# puma_tpc_sipm16.net
KiCad netlist of a schematic drawn in EAGLE
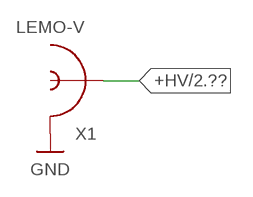
[diagram p0: schematic, sheet 1]
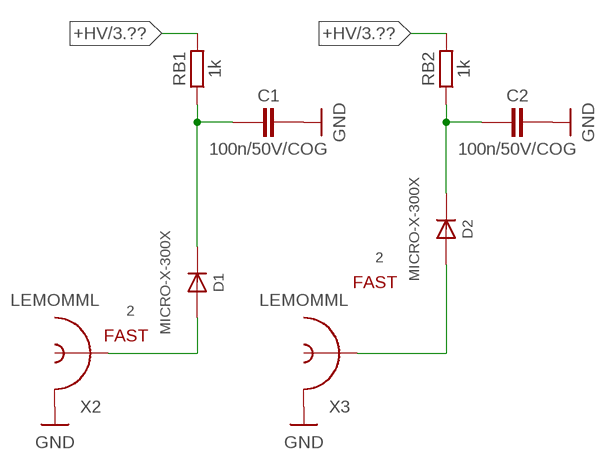
[diagram p1: schematic, sheet 2]
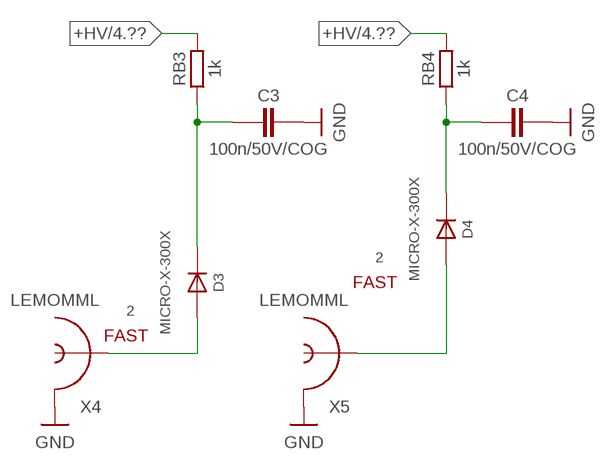
[diagram p2: schematic, sheet 3]
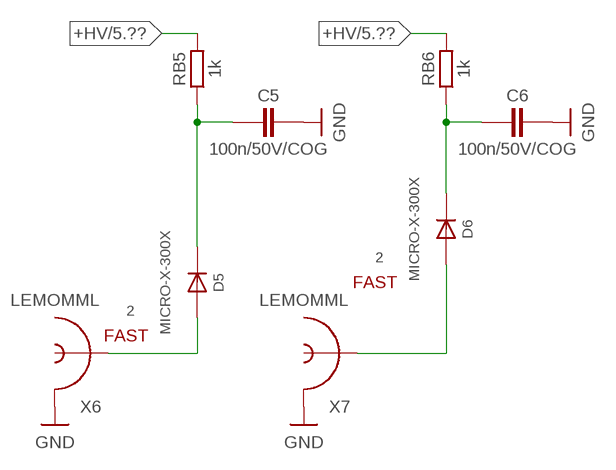
[diagram p3: schematic, sheet 4]
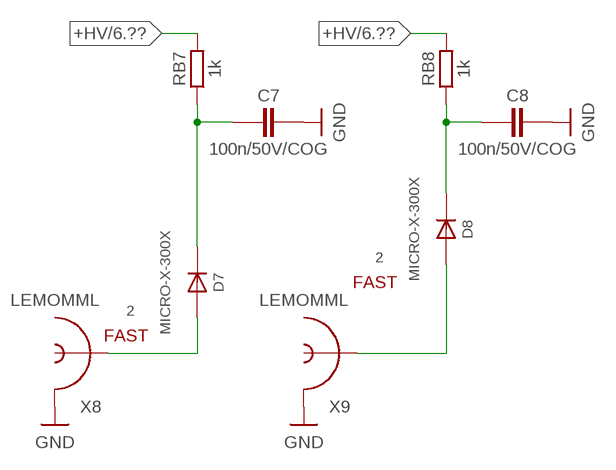
[diagram p4: schematic, sheet 5]
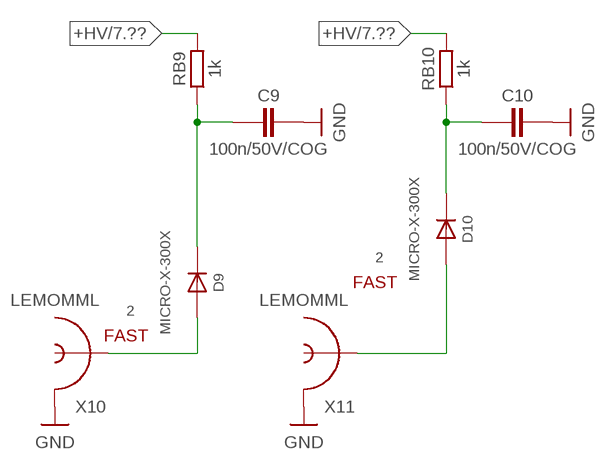
[diagram p5: schematic, sheet 6]
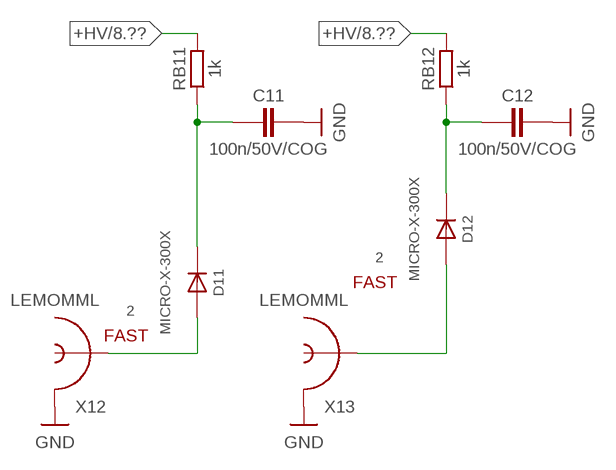
[diagram p6: schematic, sheet 7]
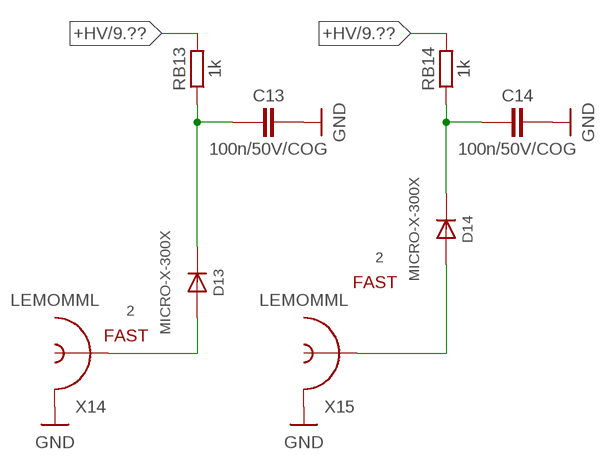
[diagram p7: schematic, sheet 8]
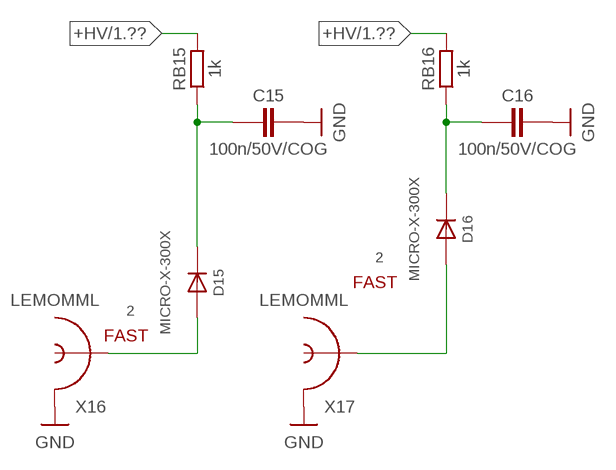
[diagram p8: schematic, sheet 9]

(export (version "E")
  (design (tool "Eeschema 10.0.6"))
  (components
    (comp (ref "C11")
      (value "100n/50V/COG")
      (footprint "eagle-import:CAP3216X130N")
      (libsource (lib "eagle-import") (part "C-EUCAP3216X130N"))
    )
    (comp (ref "C12")
      (value "100n/50V/COG")
      (footprint "eagle-import:CAP3216X130N")
      (libsource (lib "eagle-import") (part "C-EUCAP3216X130N"))
    )
    (comp (ref "D11")
      (value "MICRO-X-300X")
      (footprint "eagle-import:MICROX-300XX")
      (libsource (lib "eagle-import") (part "MICRO-?X-300X"))
    )
    (comp (ref "D12")
      (value "MICRO-X-300X")
      (footprint "eagle-import:MICROX-300XX")
      (libsource (lib "eagle-import") (part "MICRO-?X-300X"))
    )
    (comp (ref "RB11")
      (value "1k")
      (footprint "eagle-import:RES1608X55N")
      (libsource (lib "eagle-import") (part "R-EU_RES1608X55N"))
    )
    (comp (ref "RB12")
      (value "1k")
      (footprint "eagle-import:RES1608X55N")
      (libsource (lib "eagle-import") (part "R-EU_RES1608X55N"))
    )
    (comp (ref "X12")
      (value "LEMOMML")
      (footprint "eagle-import:R302.302.000")
      (libsource (lib "eagle-import") (part "LEMOMML"))
    )
    (comp (ref "X13")
      (value "LEMOMML")
      (footprint "eagle-import:R302.302.000")
      (libsource (lib "eagle-import") (part "LEMOMML"))
    )
    (comp (ref "C1")
      (value "100n/50V/COG")
      (footprint "eagle-import:CAP3216X130N")
      (libsource (lib "eagle-import") (part "C-EUCAP3216X130N"))
    )
    (comp (ref "C2")
      (value "100n/50V/COG")
      (footprint "eagle-import:CAP3216X130N")
      (libsource (lib "eagle-import") (part "C-EUCAP3216X130N"))
    )
    (comp (ref "D1")
      (value "MICRO-X-300X")
      (footprint "eagle-import:MICROX-300XX")
      (libsource (lib "eagle-import") (part "MICRO-?X-300X"))
    )
    (comp (ref "D2")
      (value "MICRO-X-300X")
      (footprint "eagle-import:MICROX-300XX")
      (libsource (lib "eagle-import") (part "MICRO-?X-300X"))
    )
    (comp (ref "RB1")
      (value "1k")
      (footprint "eagle-import:RES1608X55N")
      (libsource (lib "eagle-import") (part "R-EU_RES1608X55N"))
    )
    (comp (ref "RB2")
      (value "1k")
      (footprint "eagle-import:RES1608X55N")
      (libsource (lib "eagle-import") (part "R-EU_RES1608X55N"))
    )
    (comp (ref "X2")
      (value "LEMOMML")
      (footprint "eagle-import:R302.302.000")
      (libsource (lib "eagle-import") (part "LEMOMML"))
    )
    (comp (ref "X3")
      (value "LEMOMML")
      (footprint "eagle-import:R302.302.000")
      (libsource (lib "eagle-import") (part "LEMOMML"))
    )
    (comp (ref "C13")
      (value "100n/50V/COG")
      (footprint "eagle-import:CAP3216X130N")
      (libsource (lib "eagle-import") (part "C-EUCAP3216X130N"))
    )
    (comp (ref "C14")
      (value "100n/50V/COG")
      (footprint "eagle-import:CAP3216X130N")
      (libsource (lib "eagle-import") (part "C-EUCAP3216X130N"))
    )
    (comp (ref "D13")
      (value "MICRO-X-300X")
      (footprint "eagle-import:MICROX-300XX")
      (libsource (lib "eagle-import") (part "MICRO-?X-300X"))
    )
    (comp (ref "D14")
      (value "MICRO-X-300X")
      (footprint "eagle-import:MICROX-300XX")
      (libsource (lib "eagle-import") (part "MICRO-?X-300X"))
    )
    (comp (ref "RB13")
      (value "1k")
      (footprint "eagle-import:RES1608X55N")
      (libsource (lib "eagle-import") (part "R-EU_RES1608X55N"))
    )
    (comp (ref "RB14")
      (value "1k")
      (footprint "eagle-import:RES1608X55N")
      (libsource (lib "eagle-import") (part "R-EU_RES1608X55N"))
    )
    (comp (ref "X14")
      (value "LEMOMML")
      (footprint "eagle-import:R302.302.000")
      (libsource (lib "eagle-import") (part "LEMOMML"))
    )
    (comp (ref "X15")
      (value "LEMOMML")
      (footprint "eagle-import:R302.302.000")
      (libsource (lib "eagle-import") (part "LEMOMML"))
    )
    (comp (ref "C15")
      (value "100n/50V/COG")
      (footprint "eagle-import:CAP3216X130N")
      (libsource (lib "eagle-import") (part "C-EUCAP3216X130N"))
    )
    (comp (ref "C16")
      (value "100n/50V/COG")
      (footprint "eagle-import:CAP3216X130N")
      (libsource (lib "eagle-import") (part "C-EUCAP3216X130N"))
    )
    (comp (ref "D15")
      (value "MICRO-X-300X")
      (footprint "eagle-import:MICROX-300XX")
      (libsource (lib "eagle-import") (part "MICRO-?X-300X"))
    )
    (comp (ref "D16")
      (value "MICRO-X-300X")
      (footprint "eagle-import:MICROX-300XX")
      (libsource (lib "eagle-import") (part "MICRO-?X-300X"))
    )
    (comp (ref "RB15")
      (value "1k")
      (footprint "eagle-import:RES1608X55N")
      (libsource (lib "eagle-import") (part "R-EU_RES1608X55N"))
    )
    (comp (ref "RB16")
      (value "1k")
      (footprint "eagle-import:RES1608X55N")
      (libsource (lib "eagle-import") (part "R-EU_RES1608X55N"))
    )
    (comp (ref "X16")
      (value "LEMOMML")
      (footprint "eagle-import:R302.302.000")
      (libsource (lib "eagle-import") (part "LEMOMML"))
    )
    (comp (ref "X17")
      (value "LEMOMML")
      (footprint "eagle-import:R302.302.000")
      (libsource (lib "eagle-import") (part "LEMOMML"))
    )
    (comp (ref "X1")
      (value "LEMO-V")
      (footprint "eagle-import:LEMO-V")
      (libsource (lib "eagle-import") (part "LEMO-V"))
    )
    (comp (ref "C5")
      (value "100n/50V/COG")
      (footprint "eagle-import:CAP3216X130N")
      (libsource (lib "eagle-import") (part "C-EUCAP3216X130N"))
    )
    (comp (ref "C6")
      (value "100n/50V/COG")
      (footprint "eagle-import:CAP3216X130N")
      (libsource (lib "eagle-import") (part "C-EUCAP3216X130N"))
    )
    (comp (ref "D5")
      (value "MICRO-X-300X")
      (footprint "eagle-import:MICROX-300XX")
      (libsource (lib "eagle-import") (part "MICRO-?X-300X"))
    )
    (comp (ref "D6")
      (value "MICRO-X-300X")
      (footprint "eagle-import:MICROX-300XX")
      (libsource (lib "eagle-import") (part "MICRO-?X-300X"))
    )
    (comp (ref "RB5")
      (value "1k")
      (footprint "eagle-import:RES1608X55N")
      (libsource (lib "eagle-import") (part "R-EU_RES1608X55N"))
    )
    (comp (ref "RB6")
      (value "1k")
      (footprint "eagle-import:RES1608X55N")
      (libsource (lib "eagle-import") (part "R-EU_RES1608X55N"))
    )
    (comp (ref "X6")
      (value "LEMOMML")
      (footprint "eagle-import:R302.302.000")
      (libsource (lib "eagle-import") (part "LEMOMML"))
    )
    (comp (ref "X7")
      (value "LEMOMML")
      (footprint "eagle-import:R302.302.000")
      (libsource (lib "eagle-import") (part "LEMOMML"))
    )
    (comp (ref "C7")
      (value "100n/50V/COG")
      (footprint "eagle-import:CAP3216X130N")
      (libsource (lib "eagle-import") (part "C-EUCAP3216X130N"))
    )
    (comp (ref "C8")
      (value "100n/50V/COG")
      (footprint "eagle-import:CAP3216X130N")
      (libsource (lib "eagle-import") (part "C-EUCAP3216X130N"))
    )
    (comp (ref "D7")
      (value "MICRO-X-300X")
      (footprint "eagle-import:MICROX-300XX")
      (libsource (lib "eagle-import") (part "MICRO-?X-300X"))
    )
    (comp (ref "D8")
      (value "MICRO-X-300X")
      (footprint "eagle-import:MICROX-300XX")
      (libsource (lib "eagle-import") (part "MICRO-?X-300X"))
    )
    (comp (ref "RB7")
      (value "1k")
      (footprint "eagle-import:RES1608X55N")
      (libsource (lib "eagle-import") (part "R-EU_RES1608X55N"))
    )
    (comp (ref "RB8")
      (value "1k")
      (footprint "eagle-import:RES1608X55N")
      (libsource (lib "eagle-import") (part "R-EU_RES1608X55N"))
    )
    (comp (ref "X8")
      (value "LEMOMML")
      (footprint "eagle-import:R302.302.000")
      (libsource (lib "eagle-import") (part "LEMOMML"))
    )
    (comp (ref "X9")
      (value "LEMOMML")
      (footprint "eagle-import:R302.302.000")
      (libsource (lib "eagle-import") (part "LEMOMML"))
    )
    (comp (ref "C3")
      (value "100n/50V/COG")
      (footprint "eagle-import:CAP3216X130N")
      (libsource (lib "eagle-import") (part "C-EUCAP3216X130N"))
    )
    (comp (ref "C4")
      (value "100n/50V/COG")
      (footprint "eagle-import:CAP3216X130N")
      (libsource (lib "eagle-import") (part "C-EUCAP3216X130N"))
    )
    (comp (ref "D3")
      (value "MICRO-X-300X")
      (footprint "eagle-import:MICROX-300XX")
      (libsource (lib "eagle-import") (part "MICRO-?X-300X"))
    )
    (comp (ref "D4")
      (value "MICRO-X-300X")
      (footprint "eagle-import:MICROX-300XX")
      (libsource (lib "eagle-import") (part "MICRO-?X-300X"))
    )
    (comp (ref "RB3")
      (value "1k")
      (footprint "eagle-import:RES1608X55N")
      (libsource (lib "eagle-import") (part "R-EU_RES1608X55N"))
    )
    (comp (ref "RB4")
      (value "1k")
      (footprint "eagle-import:RES1608X55N")
      (libsource (lib "eagle-import") (part "R-EU_RES1608X55N"))
    )
    (comp (ref "X4")
      (value "LEMOMML")
      (footprint "eagle-import:R302.302.000")
      (libsource (lib "eagle-import") (part "LEMOMML"))
    )
    (comp (ref "X5")
      (value "LEMOMML")
      (footprint "eagle-import:R302.302.000")
      (libsource (lib "eagle-import") (part "LEMOMML"))
    )
    (comp (ref "C9")
      (value "100n/50V/COG")
      (footprint "eagle-import:CAP3216X130N")
      (libsource (lib "eagle-import") (part "C-EUCAP3216X130N"))
    )
    (comp (ref "C10")
      (value "100n/50V/COG")
      (footprint "eagle-import:CAP3216X130N")
      (libsource (lib "eagle-import") (part "C-EUCAP3216X130N"))
    )
    (comp (ref "D9")
      (value "MICRO-X-300X")
      (footprint "eagle-import:MICROX-300XX")
      (libsource (lib "eagle-import") (part "MICRO-?X-300X"))
    )
    (comp (ref "D10")
      (value "MICRO-X-300X")
      (footprint "eagle-import:MICROX-300XX")
      (libsource (lib "eagle-import") (part "MICRO-?X-300X"))
    )
    (comp (ref "RB9")
      (value "1k")
      (footprint "eagle-import:RES1608X55N")
      (libsource (lib "eagle-import") (part "R-EU_RES1608X55N"))
    )
    (comp (ref "RB10")
      (value "1k")
      (footprint "eagle-import:RES1608X55N")
      (libsource (lib "eagle-import") (part "R-EU_RES1608X55N"))
    )
    (comp (ref "X10")
      (value "LEMOMML")
      (footprint "eagle-import:R302.302.000")
      (libsource (lib "eagle-import") (part "LEMOMML"))
    )
    (comp (ref "X11")
      (value "LEMOMML")
      (footprint "eagle-import:R302.302.000")
      (libsource (lib "eagle-import") (part "LEMOMML"))
    )
  )
  (nets
    (net (code "1") (name "+HV") (class "Default")
      (node (ref "RB1") (pin "2") (pinfunction "2_2") (pintype "passive"))
      (node (ref "RB10") (pin "2") (pinfunction "2_2") (pintype "passive"))
      (node (ref "RB11") (pin "2") (pinfunction "2_2") (pintype "passive"))
      (node (ref "RB12") (pin "2") (pinfunction "2_2") (pintype "passive"))
      (node (ref "RB13") (pin "2") (pinfunction "2_2") (pintype "passive"))
      (node (ref "RB14") (pin "2") (pinfunction "2_2") (pintype "passive"))
      (node (ref "RB15") (pin "2") (pinfunction "2_2") (pintype "passive"))
      (node (ref "RB16") (pin "2") (pinfunction "2_2") (pintype "passive"))
      (node (ref "RB2") (pin "2") (pinfunction "2_2") (pintype "passive"))
      (node (ref "RB3") (pin "2") (pinfunction "2_2") (pintype "passive"))
      (node (ref "RB4") (pin "2") (pinfunction "2_2") (pintype "passive"))
      (node (ref "RB5") (pin "2") (pinfunction "2_2") (pintype "passive"))
      (node (ref "RB6") (pin "2") (pinfunction "2_2") (pintype "passive"))
      (node (ref "RB7") (pin "2") (pinfunction "2_2") (pintype "passive"))
      (node (ref "RB8") (pin "2") (pinfunction "2_2") (pintype "passive"))
      (node (ref "RB9") (pin "2") (pinfunction "2_2") (pintype "passive"))
      (node (ref "X1") (pin "INNER") (pinfunction "INNER_INNER") (pintype "passive"))
    )
    (net (code "2") (name "GND") (class "Default")
      (node (ref "C1") (pin "2") (pinfunction "2_2") (pintype "passive"))
      (node (ref "C10") (pin "2") (pinfunction "2_2") (pintype "passive"))
      (node (ref "C11") (pin "2") (pinfunction "2_2") (pintype "passive"))
      (node (ref "C12") (pin "2") (pinfunction "2_2") (pintype "passive"))
      (node (ref "C13") (pin "2") (pinfunction "2_2") (pintype "passive"))
      (node (ref "C14") (pin "2") (pinfunction "2_2") (pintype "passive"))
      (node (ref "C15") (pin "2") (pinfunction "2_2") (pintype "passive"))
      (node (ref "C16") (pin "2") (pinfunction "2_2") (pintype "passive"))
      (node (ref "C2") (pin "2") (pinfunction "2_2") (pintype "passive"))
      (node (ref "C3") (pin "2") (pinfunction "2_2") (pintype "passive"))
      (node (ref "C4") (pin "2") (pinfunction "2_2") (pintype "passive"))
      (node (ref "C5") (pin "2") (pinfunction "2_2") (pintype "passive"))
      (node (ref "C6") (pin "2") (pinfunction "2_2") (pintype "passive"))
      (node (ref "C7") (pin "2") (pinfunction "2_2") (pintype "passive"))
      (node (ref "C8") (pin "2") (pinfunction "2_2") (pintype "passive"))
      (node (ref "C9") (pin "2") (pinfunction "2_2") (pintype "passive"))
      (node (ref "X1") (pin "S1") (pinfunction "SHIELD_S1") (pintype "passive"))
      (node (ref "X1") (pin "S2") (pinfunction "SHIELD_S2") (pintype "passive"))
      (node (ref "X1") (pin "S3") (pinfunction "SHIELD_S3") (pintype "passive"))
      (node (ref "X1") (pin "S4") (pinfunction "SHIELD_S4") (pintype "passive"))
      (node (ref "X10") (pin "GND@1") (pinfunction "SHIELD_GND@1") (pintype "passive"))
      (node (ref "X10") (pin "GND@2") (pinfunction "SHIELD_GND@2") (pintype "passive"))
      (node (ref "X10") (pin "GND@3") (pinfunction "SHIELD_GND@3") (pintype "passive"))
      (node (ref "X11") (pin "GND@1") (pinfunction "SHIELD_GND@1") (pintype "passive"))
      (node (ref "X11") (pin "GND@2") (pinfunction "SHIELD_GND@2") (pintype "passive"))
      (node (ref "X11") (pin "GND@3") (pinfunction "SHIELD_GND@3") (pintype "passive"))
      (node (ref "X12") (pin "GND@1") (pinfunction "SHIELD_GND@1") (pintype "passive"))
      (node (ref "X12") (pin "GND@2") (pinfunction "SHIELD_GND@2") (pintype "passive"))
      (node (ref "X12") (pin "GND@3") (pinfunction "SHIELD_GND@3") (pintype "passive"))
      (node (ref "X13") (pin "GND@1") (pinfunction "SHIELD_GND@1") (pintype "passive"))
      (node (ref "X13") (pin "GND@2") (pinfunction "SHIELD_GND@2") (pintype "passive"))
      (node (ref "X13") (pin "GND@3") (pinfunction "SHIELD_GND@3") (pintype "passive"))
      (node (ref "X14") (pin "GND@1") (pinfunction "SHIELD_GND@1") (pintype "passive"))
      (node (ref "X14") (pin "GND@2") (pinfunction "SHIELD_GND@2") (pintype "passive"))
      (node (ref "X14") (pin "GND@3") (pinfunction "SHIELD_GND@3") (pintype "passive"))
      (node (ref "X15") (pin "GND@1") (pinfunction "SHIELD_GND@1") (pintype "passive"))
      (node (ref "X15") (pin "GND@2") (pinfunction "SHIELD_GND@2") (pintype "passive"))
      (node (ref "X15") (pin "GND@3") (pinfunction "SHIELD_GND@3") (pintype "passive"))
      (node (ref "X16") (pin "GND@1") (pinfunction "SHIELD_GND@1") (pintype "passive"))
      (node (ref "X16") (pin "GND@2") (pinfunction "SHIELD_GND@2") (pintype "passive"))
      (node (ref "X16") (pin "GND@3") (pinfunction "SHIELD_GND@3") (pintype "passive"))
      (node (ref "X17") (pin "GND@1") (pinfunction "SHIELD_GND@1") (pintype "passive"))
      (node (ref "X17") (pin "GND@2") (pinfunction "SHIELD_GND@2") (pintype "passive"))
      (node (ref "X17") (pin "GND@3") (pinfunction "SHIELD_GND@3") (pintype "passive"))
      (node (ref "X2") (pin "GND@1") (pinfunction "SHIELD_GND@1") (pintype "passive"))
      (node (ref "X2") (pin "GND@2") (pinfunction "SHIELD_GND@2") (pintype "passive"))
      (node (ref "X2") (pin "GND@3") (pinfunction "SHIELD_GND@3") (pintype "passive"))
      (node (ref "X3") (pin "GND@1") (pinfunction "SHIELD_GND@1") (pintype "passive"))
      (node (ref "X3") (pin "GND@2") (pinfunction "SHIELD_GND@2") (pintype "passive"))
      (node (ref "X3") (pin "GND@3") (pinfunction "SHIELD_GND@3") (pintype "passive"))
      (node (ref "X4") (pin "GND@1") (pinfunction "SHIELD_GND@1") (pintype "passive"))
      (node (ref "X4") (pin "GND@2") (pinfunction "SHIELD_GND@2") (pintype "passive"))
      (node (ref "X4") (pin "GND@3") (pinfunction "SHIELD_GND@3") (pintype "passive"))
      (node (ref "X5") (pin "GND@1") (pinfunction "SHIELD_GND@1") (pintype "passive"))
      (node (ref "X5") (pin "GND@2") (pinfunction "SHIELD_GND@2") (pintype "passive"))
      (node (ref "X5") (pin "GND@3") (pinfunction "SHIELD_GND@3") (pintype "passive"))
      (node (ref "X6") (pin "GND@1") (pinfunction "SHIELD_GND@1") (pintype "passive"))
      (node (ref "X6") (pin "GND@2") (pinfunction "SHIELD_GND@2") (pintype "passive"))
      (node (ref "X6") (pin "GND@3") (pinfunction "SHIELD_GND@3") (pintype "passive"))
      (node (ref "X7") (pin "GND@1") (pinfunction "SHIELD_GND@1") (pintype "passive"))
      (node (ref "X7") (pin "GND@2") (pinfunction "SHIELD_GND@2") (pintype "passive"))
      (node (ref "X7") (pin "GND@3") (pinfunction "SHIELD_GND@3") (pintype "passive"))
      (node (ref "X8") (pin "GND@1") (pinfunction "SHIELD_GND@1") (pintype "passive"))
      (node (ref "X8") (pin "GND@2") (pinfunction "SHIELD_GND@2") (pintype "passive"))
      (node (ref "X8") (pin "GND@3") (pinfunction "SHIELD_GND@3") (pintype "passive"))
      (node (ref "X9") (pin "GND@1") (pinfunction "SHIELD_GND@1") (pintype "passive"))
      (node (ref "X9") (pin "GND@2") (pinfunction "SHIELD_GND@2") (pintype "passive"))
      (node (ref "X9") (pin "GND@3") (pinfunction "SHIELD_GND@3") (pintype "passive"))
    )
    (net (code "3") (name "Net-(D1-A)") (class "Default")
      (node (ref "D1") (pin "1") (pinfunction "A_1") (pintype "passive"))
      (node (ref "X2") (pin "1") (pinfunction "INNER_1") (pintype "passive"))
    )
    (net (code "4") (name "Net-(D1-K)") (class "Default")
      (node (ref "C1") (pin "1") (pinfunction "1_1") (pintype "passive"))
      (node (ref "D1") (pin "3") (pinfunction "K_3") (pintype "passive"))
      (node (ref "RB1") (pin "1") (pinfunction "1_1") (pintype "passive"))
    )
    (net (code "5") (name "Net-(D2-A)") (class "Default")
      (node (ref "D2") (pin "1") (pinfunction "A_1") (pintype "passive"))
      (node (ref "X3") (pin "1") (pinfunction "INNER_1") (pintype "passive"))
    )
    (net (code "6") (name "Net-(D2-K)") (class "Default")
      (node (ref "C2") (pin "1") (pinfunction "1_1") (pintype "passive"))
      (node (ref "D2") (pin "3") (pinfunction "K_3") (pintype "passive"))
      (node (ref "RB2") (pin "1") (pinfunction "1_1") (pintype "passive"))
    )
    (net (code "7") (name "Net-(D3-A)") (class "Default")
      (node (ref "D3") (pin "1") (pinfunction "A_1") (pintype "passive"))
      (node (ref "X4") (pin "1") (pinfunction "INNER_1") (pintype "passive"))
    )
    (net (code "8") (name "Net-(D3-K)") (class "Default")
      (node (ref "C3") (pin "1") (pinfunction "1_1") (pintype "passive"))
      (node (ref "D3") (pin "3") (pinfunction "K_3") (pintype "passive"))
      (node (ref "RB3") (pin "1") (pinfunction "1_1") (pintype "passive"))
    )
    (net (code "9") (name "Net-(D4-A)") (class "Default")
      (node (ref "D4") (pin "1") (pinfunction "A_1") (pintype "passive"))
      (node (ref "X5") (pin "1") (pinfunction "INNER_1") (pintype "passive"))
    )
    (net (code "10") (name "Net-(D4-K)") (class "Default")
      (node (ref "C4") (pin "1") (pinfunction "1_1") (pintype "passive"))
      (node (ref "D4") (pin "3") (pinfunction "K_3") (pintype "passive"))
      (node (ref "RB4") (pin "1") (pinfunction "1_1") (pintype "passive"))
    )
    (net (code "11") (name "Net-(D5-A)") (class "Default")
      (node (ref "D5") (pin "1") (pinfunction "A_1") (pintype "passive"))
      (node (ref "X6") (pin "1") (pinfunction "INNER_1") (pintype "passive"))
    )
    (net (code "12") (name "Net-(D5-K)") (class "Default")
      (node (ref "C5") (pin "1") (pinfunction "1_1") (pintype "passive"))
      (node (ref "D5") (pin "3") (pinfunction "K_3") (pintype "passive"))
      (node (ref "RB5") (pin "1") (pinfunction "1_1") (pintype "passive"))
    )
    (net (code "13") (name "Net-(D6-A)") (class "Default")
      (node (ref "D6") (pin "1") (pinfunction "A_1") (pintype "passive"))
      (node (ref "X7") (pin "1") (pinfunction "INNER_1") (pintype "passive"))
    )
    (net (code "14") (name "Net-(D6-K)") (class "Default")
      (node (ref "C6") (pin "1") (pinfunction "1_1") (pintype "passive"))
      (node (ref "D6") (pin "3") (pinfunction "K_3") (pintype "passive"))
      (node (ref "RB6") (pin "1") (pinfunction "1_1") (pintype "passive"))
    )
    (net (code "15") (name "Net-(D7-A)") (class "Default")
      (node (ref "D7") (pin "1") (pinfunction "A_1") (pintype "passive"))
      (node (ref "X8") (pin "1") (pinfunction "INNER_1") (pintype "passive"))
    )
    (net (code "16") (name "Net-(D7-K)") (class "Default")
      (node (ref "C7") (pin "1") (pinfunction "1_1") (pintype "passive"))
      (node (ref "D7") (pin "3") (pinfunction "K_3") (pintype "passive"))
      (node (ref "RB7") (pin "1") (pinfunction "1_1") (pintype "passive"))
    )
    (net (code "17") (name "Net-(D8-A)") (class "Default")
      (node (ref "D8") (pin "1") (pinfunction "A_1") (pintype "passive"))
      (node (ref "X9") (pin "1") (pinfunction "INNER_1") (pintype "passive"))
    )
    (net (code "18") (name "Net-(D8-K)") (class "Default")
      (node (ref "C8") (pin "1") (pinfunction "1_1") (pintype "passive"))
      (node (ref "D8") (pin "3") (pinfunction "K_3") (pintype "passive"))
      (node (ref "RB8") (pin "1") (pinfunction "1_1") (pintype "passive"))
    )
    (net (code "19") (name "Net-(D9-A)") (class "Default")
      (node (ref "D9") (pin "1") (pinfunction "A_1") (pintype "passive"))
      (node (ref "X10") (pin "1") (pinfunction "INNER_1") (pintype "passive"))
    )
    (net (code "20") (name "Net-(D9-K)") (class "Default")
      (node (ref "C9") (pin "1") (pinfunction "1_1") (pintype "passive"))
      (node (ref "D9") (pin "3") (pinfunction "K_3") (pintype "passive"))
      (node (ref "RB9") (pin "1") (pinfunction "1_1") (pintype "passive"))
    )
    (net (code "21") (name "Net-(D10-A)") (class "Default")
      (node (ref "D10") (pin "1") (pinfunction "A_1") (pintype "passive"))
      (node (ref "X11") (pin "1") (pinfunction "INNER_1") (pintype "passive"))
    )
    (net (code "22") (name "Net-(D10-K)") (class "Default")
      (node (ref "C10") (pin "1") (pinfunction "1_1") (pintype "passive"))
      (node (ref "D10") (pin "3") (pinfunction "K_3") (pintype "passive"))
      (node (ref "RB10") (pin "1") (pinfunction "1_1") (pintype "passive"))
    )
    (net (code "23") (name "Net-(D11-A)") (class "Default")
      (node (ref "D11") (pin "1") (pinfunction "A_1") (pintype "passive"))
      (node (ref "X12") (pin "1") (pinfunction "INNER_1") (pintype "passive"))
    )
    (net (code "24") (name "Net-(D11-K)") (class "Default")
      (node (ref "C11") (pin "1") (pinfunction "1_1") (pintype "passive"))
      (node (ref "D11") (pin "3") (pinfunction "K_3") (pintype "passive"))
      (node (ref "RB11") (pin "1") (pinfunction "1_1") (pintype "passive"))
    )
    (net (code "25") (name "Net-(D12-A)") (class "Default")
      (node (ref "D12") (pin "1") (pinfunction "A_1") (pintype "passive"))
      (node (ref "X13") (pin "1") (pinfunction "INNER_1") (pintype "passive"))
    )
    (net (code "26") (name "Net-(D12-K)") (class "Default")
      (node (ref "C12") (pin "1") (pinfunction "1_1") (pintype "passive"))
      (node (ref "D12") (pin "3") (pinfunction "K_3") (pintype "passive"))
      (node (ref "RB12") (pin "1") (pinfunction "1_1") (pintype "passive"))
    )
    (net (code "27") (name "Net-(D13-A)") (class "Default")
      (node (ref "D13") (pin "1") (pinfunction "A_1") (pintype "passive"))
      (node (ref "X14") (pin "1") (pinfunction "INNER_1") (pintype "passive"))
    )
    (net (code "28") (name "Net-(D13-K)") (class "Default")
      (node (ref "C13") (pin "1") (pinfunction "1_1") (pintype "passive"))
      (node (ref "D13") (pin "3") (pinfunction "K_3") (pintype "passive"))
      (node (ref "RB13") (pin "1") (pinfunction "1_1") (pintype "passive"))
    )
    (net (code "29") (name "Net-(D14-A)") (class "Default")
      (node (ref "D14") (pin "1") (pinfunction "A_1") (pintype "passive"))
      (node (ref "X15") (pin "1") (pinfunction "INNER_1") (pintype "passive"))
    )
    (net (code "30") (name "Net-(D14-K)") (class "Default")
      (node (ref "C14") (pin "1") (pinfunction "1_1") (pintype "passive"))
      (node (ref "D14") (pin "3") (pinfunction "K_3") (pintype "passive"))
      (node (ref "RB14") (pin "1") (pinfunction "1_1") (pintype "passive"))
    )
    (net (code "31") (name "Net-(D15-A)") (class "Default")
      (node (ref "D15") (pin "1") (pinfunction "A_1") (pintype "passive"))
      (node (ref "X16") (pin "1") (pinfunction "INNER_1") (pintype "passive"))
    )
    (net (code "32") (name "Net-(D15-K)") (class "Default")
      (node (ref "C15") (pin "1") (pinfunction "1_1") (pintype "passive"))
      (node (ref "D15") (pin "3") (pinfunction "K_3") (pintype "passive"))
      (node (ref "RB15") (pin "1") (pinfunction "1_1") (pintype "passive"))
    )
    (net (code "33") (name "Net-(D16-A)") (class "Default")
      (node (ref "D16") (pin "1") (pinfunction "A_1") (pintype "passive"))
      (node (ref "X17") (pin "1") (pinfunction "INNER_1") (pintype "passive"))
    )
    (net (code "34") (name "Net-(D16-K)") (class "Default")
      (node (ref "C16") (pin "1") (pinfunction "1_1") (pintype "passive"))
      (node (ref "D16") (pin "3") (pinfunction "K_3") (pintype "passive"))
      (node (ref "RB16") (pin "1") (pinfunction "1_1") (pintype "passive"))
    )
    (net (code "35") (name "unconnected-(D1-FAST-Pad2)") (class "Default")
      (node (ref "D1") (pin "2") (pinfunction "FAST_2") (pintype "passive"))
    )
    (net (code "36") (name "unconnected-(D1-NC-Pad4)") (class "Default")
      (node (ref "D1") (pin "4") (pinfunction "NC_4") (pintype "passive"))
    )
    (net (code "37") (name "unconnected-(D2-FAST-Pad2)") (class "Default")
      (node (ref "D2") (pin "2") (pinfunction "FAST_2") (pintype "passive"))
    )
    (net (code "38") (name "unconnected-(D2-NC-Pad4)") (class "Default")
      (node (ref "D2") (pin "4") (pinfunction "NC_4") (pintype "passive"))
    )
    (net (code "39") (name "unconnected-(D3-FAST-Pad2)") (class "Default")
      (node (ref "D3") (pin "2") (pinfunction "FAST_2") (pintype "passive"))
    )
    (net (code "40") (name "unconnected-(D3-NC-Pad4)") (class "Default")
      (node (ref "D3") (pin "4") (pinfunction "NC_4") (pintype "passive"))
    )
    (net (code "41") (name "unconnected-(D4-FAST-Pad2)") (class "Default")
      (node (ref "D4") (pin "2") (pinfunction "FAST_2") (pintype "passive"))
    )
    (net (code "42") (name "unconnected-(D4-NC-Pad4)") (class "Default")
      (node (ref "D4") (pin "4") (pinfunction "NC_4") (pintype "passive"))
    )
    (net (code "43") (name "unconnected-(D5-FAST-Pad2)") (class "Default")
      (node (ref "D5") (pin "2") (pinfunction "FAST_2") (pintype "passive"))
    )
    (net (code "44") (name "unconnected-(D5-NC-Pad4)") (class "Default")
      (node (ref "D5") (pin "4") (pinfunction "NC_4") (pintype "passive"))
    )
    (net (code "45") (name "unconnected-(D6-FAST-Pad2)") (class "Default")
      (node (ref "D6") (pin "2") (pinfunction "FAST_2") (pintype "passive"))
    )
    (net (code "46") (name "unconnected-(D6-NC-Pad4)") (class "Default")
      (node (ref "D6") (pin "4") (pinfunction "NC_4") (pintype "passive"))
    )
    (net (code "47") (name "unconnected-(D7-FAST-Pad2)") (class "Default")
      (node (ref "D7") (pin "2") (pinfunction "FAST_2") (pintype "passive"))
    )
    (net (code "48") (name "unconnected-(D7-NC-Pad4)") (class "Default")
      (node (ref "D7") (pin "4") (pinfunction "NC_4") (pintype "passive"))
    )
    (net (code "49") (name "unconnected-(D8-FAST-Pad2)") (class "Default")
      (node (ref "D8") (pin "2") (pinfunction "FAST_2") (pintype "passive"))
    )
    (net (code "50") (name "unconnected-(D8-NC-Pad4)") (class "Default")
      (node (ref "D8") (pin "4") (pinfunction "NC_4") (pintype "passive"))
    )
    (net (code "51") (name "unconnected-(D9-FAST-Pad2)") (class "Default")
      (node (ref "D9") (pin "2") (pinfunction "FAST_2") (pintype "passive"))
    )
    (net (code "52") (name "unconnected-(D9-NC-Pad4)") (class "Default")
      (node (ref "D9") (pin "4") (pinfunction "NC_4") (pintype "passive"))
    )
    (net (code "53") (name "unconnected-(D10-FAST-Pad2)") (class "Default")
      (node (ref "D10") (pin "2") (pinfunction "FAST_2") (pintype "passive"))
    )
    (net (code "54") (name "unconnected-(D10-NC-Pad4)") (class "Default")
      (node (ref "D10") (pin "4") (pinfunction "NC_4") (pintype "passive"))
    )
    (net (code "55") (name "unconnected-(D11-FAST-Pad2)") (class "Default")
      (node (ref "D11") (pin "2") (pinfunction "FAST_2") (pintype "passive"))
    )
    (net (code "56") (name "unconnected-(D11-NC-Pad4)") (class "Default")
      (node (ref "D11") (pin "4") (pinfunction "NC_4") (pintype "passive"))
    )
    (net (code "57") (name "unconnected-(D12-FAST-Pad2)") (class "Default")
      (node (ref "D12") (pin "2") (pinfunction "FAST_2") (pintype "passive"))
    )
    (net (code "58") (name "unconnected-(D12-NC-Pad4)") (class "Default")
      (node (ref "D12") (pin "4") (pinfunction "NC_4") (pintype "passive"))
    )
    (net (code "59") (name "unconnected-(D13-FAST-Pad2)") (class "Default")
      (node (ref "D13") (pin "2") (pinfunction "FAST_2") (pintype "passive"))
    )
    (net (code "60") (name "unconnected-(D13-NC-Pad4)") (class "Default")
      (node (ref "D13") (pin "4") (pinfunction "NC_4") (pintype "passive"))
    )
    (net (code "61") (name "unconnected-(D14-FAST-Pad2)") (class "Default")
      (node (ref "D14") (pin "2") (pinfunction "FAST_2") (pintype "passive"))
    )
    (net (code "62") (name "unconnected-(D14-NC-Pad4)") (class "Default")
      (node (ref "D14") (pin "4") (pinfunction "NC_4") (pintype "passive"))
    )
    (net (code "63") (name "unconnected-(D15-FAST-Pad2)") (class "Default")
      (node (ref "D15") (pin "2") (pinfunction "FAST_2") (pintype "passive"))
    )
    (net (code "64") (name "unconnected-(D15-NC-Pad4)") (class "Default")
      (node (ref "D15") (pin "4") (pinfunction "NC_4") (pintype "passive"))
    )
    (net (code "65") (name "unconnected-(D16-FAST-Pad2)") (class "Default")
      (node (ref "D16") (pin "2") (pinfunction "FAST_2") (pintype "passive"))
    )
    (net (code "66") (name "unconnected-(D16-NC-Pad4)") (class "Default")
      (node (ref "D16") (pin "4") (pinfunction "NC_4") (pintype "passive"))
    )
  )
)
